# 12_-_CONNECTOR.net
KiCad netlist of a schematic drawn in Altium Designer
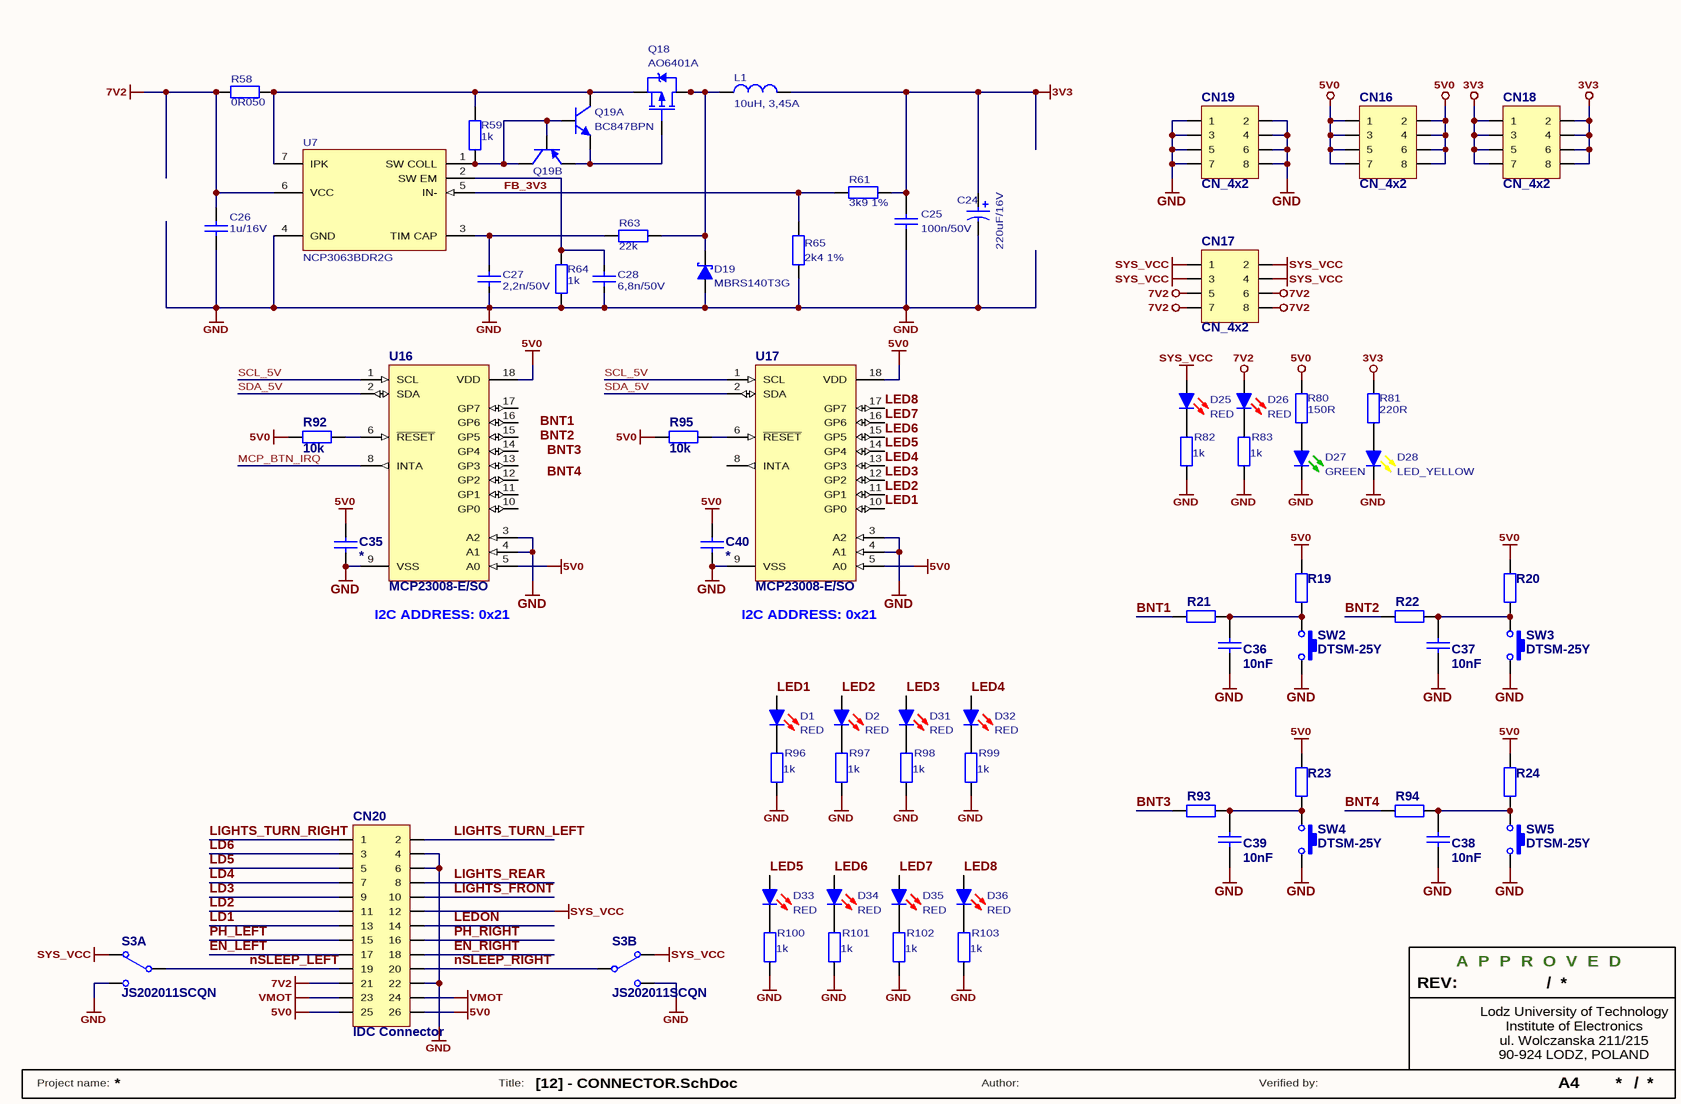
[diagram p0: [12] - CONNECTOR.SchDoc]

(export (version "E")
  (design (tool "Eeschema 10.0.6"))
  (components
    (comp (ref "C24")
      (value "220uF/16V")
      (footprint "CES_E_8.3x8.3_6.2")
      (description "Polarized Capacitor")
      (libsource (lib "capacitors") (part "Cap Pol"))
    )
    (comp (ref "C25")
      (value "100n/50V")
      (footprint "C0805")
      (description "Capacitor")
      (libsource (lib "capacitors") (part "Cap"))
    )
    (comp (ref "C26")
      (value "1u/16V")
      (footprint "C0805")
      (description "Capacitor")
      (libsource (lib "") (part "Cap_2"))
    )
    (comp (ref "C27")
      (value "2,2n/50V")
      (footprint "C0805")
      (description "Capacitor")
      (libsource (lib "") (part "Cap_1"))
    )
    (comp (ref "C28")
      (value "6,8n/50V")
      (footprint "C0805")
      (description "Capacitor")
      (libsource (lib "") (part "Cap_1"))
    )
    (comp (ref "C35")
      (value "*")
      (footprint "C0805")
      (description "Capacitor")
      (fields (field (name "ALTIUM_VALUE") "*"))
      (libsource (lib "") (part "Cap_2"))
    )
    (comp (ref "C36")
      (value "10nF")
      (footprint "C0805")
      (description "Capacitor")
      (libsource (lib "capacitors") (part "Cap"))
    )
    (comp (ref "C37")
      (value "10nF")
      (footprint "C0805")
      (description "Capacitor")
      (libsource (lib "capacitors") (part "Cap"))
    )
    (comp (ref "C38")
      (value "10nF")
      (footprint "C0805")
      (description "Capacitor")
      (libsource (lib "capacitors") (part "Cap"))
    )
    (comp (ref "C39")
      (value "10nF")
      (footprint "C0805")
      (description "Capacitor")
      (libsource (lib "capacitors") (part "Cap"))
    )
    (comp (ref "C40")
      (value "*")
      (footprint "C0805")
      (description "Capacitor")
      (fields (field (name "ALTIUM_VALUE") "*"))
      (libsource (lib "") (part "Cap_2"))
    )
    (comp (ref "CN16") (value "CN_4x2") (footprint "GP_4x2") (libsource (lib "goldpin_male") (part "CN_4x2")))
    (comp (ref "CN17") (value "CN_4x2") (footprint "GP_4x2") (libsource (lib "goldpin_male") (part "CN_4x2")))
    (comp (ref "CN18") (value "CN_4x2") (footprint "GP_4x2") (libsource (lib "goldpin_male") (part "CN_4x2")))
    (comp (ref "CN19") (value "CN_4x2") (footprint "GP_4x2") (libsource (lib "goldpin_male") (part "CN_4x2")))
    (comp (ref "CN20")
      (value "IDC Connector")
      (footprint "IDC26_RA")
      (libsource (lib "idc") (part "CN_13x2"))
    )
    (comp (ref "D1")
      (value "RED")
      (footprint "LED0805R")
      (description "RED LED")
      (libsource (lib "leds") (part "LED_RED"))
    )
    (comp (ref "D2")
      (value "RED")
      (footprint "LED0805R")
      (description "RED LED")
      (libsource (lib "leds") (part "LED_RED"))
    )
    (comp (ref "D19")
      (value "MBRS140T3G")
      (footprint "SMB")
      (description "Schottky barrier rectifier: 40V, 1A")
      (libsource (lib "diodes_schottky") (part "MBRS140T3G"))
    )
    (comp (ref "D25")
      (value "RED")
      (footprint "LED0805R")
      (description "RED LED")
      (libsource (lib "leds") (part "LED_RED"))
    )
    (comp (ref "D26")
      (value "RED")
      (footprint "LED0805R")
      (description "RED LED")
      (libsource (lib "leds") (part "LED_RED"))
    )
    (comp (ref "D27")
      (value "GREEN")
      (footprint "LED0805G")
      (description "GREEN LED")
      (libsource (lib "leds") (part "LED_GREEN"))
    )
    (comp (ref "D28")
      (value "LED_YELLOW")
      (footprint "LED0805Y")
      (description "YELLOW LED")
      (libsource (lib "leds") (part "LED_YELLOW"))
    )
    (comp (ref "D31")
      (value "RED")
      (footprint "LED0805R")
      (description "RED LED")
      (libsource (lib "leds") (part "LED_RED"))
    )
    (comp (ref "D32")
      (value "RED")
      (footprint "LED0805R")
      (description "RED LED")
      (libsource (lib "leds") (part "LED_RED"))
    )
    (comp (ref "D33")
      (value "RED")
      (footprint "LED0805R")
      (description "RED LED")
      (libsource (lib "leds") (part "LED_RED"))
    )
    (comp (ref "D34")
      (value "RED")
      (footprint "LED0805R")
      (description "RED LED")
      (libsource (lib "leds") (part "LED_RED"))
    )
    (comp (ref "D35")
      (value "RED")
      (footprint "LED0805R")
      (description "RED LED")
      (libsource (lib "leds") (part "LED_RED"))
    )
    (comp (ref "D36")
      (value "RED")
      (footprint "LED0805R")
      (description "RED LED")
      (libsource (lib "leds") (part "LED_RED"))
    )
    (comp (ref "L1")
      (value "10uH, 3,45A")
      (footprint "PSDB1005")
      (description "10uH, 20%, 3,45A, PSDB1005N Series Inductor")
      (libsource (lib "inductors") (part "PSDB1005NT100"))
    )
    (comp (ref "Q18")
      (value "AO6401A")
      (footprint "SOT-23-6")
      (description "P-Channel MOSFET; -60V, -5A, 1.3W;")
      (libsource (lib "transistors_mos") (part "AO6401A"))
    )
    (comp (ref "Q19")
      (value "BC847BPN")
      (footprint "SOT-323-6 (SOT-363, SC88, SC70-6)")
      (description "PNP/NPN General Purpose Transistor (VCE=45V, IC=100mA)")
      (libsource (lib "transistors_bjt") (part "BC847BPN"))
    )
    (comp (ref "R19")
      (value "~")
      (footprint "R0805")
      (description "Resistor")
      (libsource (lib "") (part "Res_1"))
    )
    (comp (ref "R20")
      (value "~")
      (footprint "R0805")
      (description "Resistor")
      (libsource (lib "") (part "Res_1"))
    )
    (comp (ref "R21")
      (value "~")
      (footprint "R0805")
      (description "Resistor")
      (libsource (lib "") (part "Res_4"))
    )
    (comp (ref "R22")
      (value "~")
      (footprint "R0805")
      (description "Resistor")
      (libsource (lib "") (part "Res_4"))
    )
    (comp (ref "R23")
      (value "~")
      (footprint "R0805")
      (description "Resistor")
      (libsource (lib "") (part "Res_1"))
    )
    (comp (ref "R24")
      (value "~")
      (footprint "R0805")
      (description "Resistor")
      (libsource (lib "") (part "Res_1"))
    )
    (comp (ref "R58")
      (value "0R050")
      (footprint "R0805")
      (description "Resistor")
      (libsource (lib "") (part "Res_3"))
    )
    (comp (ref "R59")
      (value "1k")
      (footprint "R0805")
      (description "Resistor")
      (libsource (lib "resistors") (part "Res"))
    )
    (comp (ref "R61")
      (value "3k9 1%")
      (footprint "R0805")
      (description "Resistor")
      (libsource (lib "") (part "Res_3"))
    )
    (comp (ref "R63")
      (value "22k")
      (footprint "R0805")
      (description "Resistor")
      (libsource (lib "") (part "Res_2"))
    )
    (comp (ref "R64")
      (value "1k")
      (footprint "R0805")
      (description "Resistor")
      (libsource (lib "resistors") (part "Res"))
    )
    (comp (ref "R65")
      (value "2k4 1%")
      (footprint "R0805")
      (description "Resistor")
      (libsource (lib "resistors") (part "Res"))
    )
    (comp (ref "R80")
      (value "150R")
      (footprint "R0805")
      (description "Resistor")
      (libsource (lib "resistors") (part "Res"))
    )
    (comp (ref "R81")
      (value "220R")
      (footprint "R0805")
      (description "Resistor")
      (libsource (lib "resistors") (part "Res"))
    )
    (comp (ref "R82")
      (value "1k")
      (footprint "R0805")
      (description "Resistor")
      (libsource (lib "resistors") (part "Res"))
    )
    (comp (ref "R83")
      (value "1k")
      (footprint "R0805")
      (description "Resistor")
      (libsource (lib "resistors") (part "Res"))
    )
    (comp (ref "R92")
      (value "10k")
      (footprint "R0805")
      (description "Resistor")
      (libsource (lib "") (part "Res_3"))
    )
    (comp (ref "R93")
      (value "~")
      (footprint "R0805")
      (description "Resistor")
      (libsource (lib "") (part "Res_4"))
    )
    (comp (ref "R94")
      (value "~")
      (footprint "R0805")
      (description "Resistor")
      (libsource (lib "") (part "Res_4"))
    )
    (comp (ref "R95")
      (value "10k")
      (footprint "R0805")
      (description "Resistor")
      (libsource (lib "") (part "Res_3"))
    )
    (comp (ref "R96")
      (value "1k")
      (footprint "R0805")
      (description "Resistor")
      (libsource (lib "resistors") (part "Res"))
    )
    (comp (ref "R97")
      (value "1k")
      (footprint "R0805")
      (description "Resistor")
      (libsource (lib "resistors") (part "Res"))
    )
    (comp (ref "R98")
      (value "1k")
      (footprint "R0805")
      (description "Resistor")
      (libsource (lib "resistors") (part "Res"))
    )
    (comp (ref "R99")
      (value "1k")
      (footprint "R0805")
      (description "Resistor")
      (libsource (lib "resistors") (part "Res"))
    )
    (comp (ref "R100")
      (value "1k")
      (footprint "R0805")
      (description "Resistor")
      (libsource (lib "resistors") (part "Res"))
    )
    (comp (ref "R101")
      (value "1k")
      (footprint "R0805")
      (description "Resistor")
      (libsource (lib "resistors") (part "Res"))
    )
    (comp (ref "R102")
      (value "1k")
      (footprint "R0805")
      (description "Resistor")
      (libsource (lib "resistors") (part "Res"))
    )
    (comp (ref "R103")
      (value "1k")
      (footprint "R0805")
      (description "Resistor")
      (libsource (lib "resistors") (part "Res"))
    )
    (comp (ref "S3")
      (value "JS202011SCQN")
      (footprint "JS202011SCQN")
      (description "C&K JS202011SCQN DPDT Switch")
      (fields (field (name "PUBLISHER") "Altium Limited"))
      (libsource (lib "switches_slide") (part "JS202011SCQN"))
    )
    (comp (ref "SW2")
      (value "DTSM-25Y")
      (footprint "DTSM-25Y")
      (description "DIPTRONICS Yellow 12x12mm SMD Tactile SPST-NO Switch")
      (libsource (lib "microswitches") (part "DTSM-25Y"))
    )
    (comp (ref "SW3")
      (value "DTSM-25Y")
      (footprint "DTSM-25Y")
      (description "DIPTRONICS Yellow 12x12mm SMD Tactile SPST-NO Switch")
      (libsource (lib "microswitches") (part "DTSM-25Y"))
    )
    (comp (ref "SW4")
      (value "DTSM-25Y")
      (footprint "DTSM-25Y")
      (description "DIPTRONICS Yellow 12x12mm SMD Tactile SPST-NO Switch")
      (libsource (lib "microswitches") (part "DTSM-25Y"))
    )
    (comp (ref "SW5")
      (value "DTSM-25Y")
      (footprint "DTSM-25Y")
      (description "DIPTRONICS Yellow 12x12mm SMD Tactile SPST-NO Switch")
      (libsource (lib "microswitches") (part "DTSM-25Y"))
    )
    (comp (ref "U7")
      (value "NCP3063BDR2G")
      (footprint "SO8")
      (description "DC-DC Converter NCP3063BDR2G (Farnell 1547126)")
      (libsource (lib "switched_voltage_regulators") (part "NCP3063BDR2G"))
    )
    (comp (ref "U16")
      (value "MCP23008-E/SO")
      (footprint "SO18W")
      (description "8-Bit I/O Expander with Serial Interface I2C, 18-Pin SOIC Package")
      (libsource (lib "io_expanders") (part "MCP23008-E/SO"))
    )
    (comp (ref "U17")
      (value "MCP23008-E/SO")
      (footprint "SO18W")
      (description "8-Bit I/O Expander with Serial Interface I2C, 18-Pin SOIC Package")
      (libsource (lib "io_expanders") (part "MCP23008-E/SO"))
    )
  )
  (nets
    (net (code "1") (name "/BNT1") (class "Default")
      (node (ref "R21") (pin "1") (pinfunction "1_1") (pintype "passive"))
    )
    (net (code "2") (name "/BNT2") (class "Default")
      (node (ref "R22") (pin "1") (pinfunction "1_1") (pintype "passive"))
    )
    (net (code "3") (name "/BNT3") (class "Default")
      (node (ref "R93") (pin "1") (pinfunction "1_1") (pintype "passive"))
    )
    (net (code "4") (name "/BNT4") (class "Default")
      (node (ref "R94") (pin "1") (pinfunction "1_1") (pintype "passive"))
    )
    (net (code "5") (name "/EN_LEFT") (class "Default")
      (node (ref "CN20") (pin "17") (pinfunction "17_17") (pintype "passive"))
    )
    (net (code "6") (name "/EN_RIGHT") (class "Default")
      (node (ref "CN20") (pin "18") (pinfunction "18_18") (pintype "passive"))
    )
    (net (code "7") (name "/FB_3V3") (class "Default")
      (node (ref "R61") (pin "1") (pinfunction "1_1") (pintype "passive"))
      (node (ref "R65") (pin "1") (pinfunction "1_1") (pintype "passive"))
      (node (ref "U7") (pin "5") (pinfunction "IN-_5") (pintype "input"))
    )
    (net (code "8") (name "/LD1") (class "Default")
      (node (ref "CN20") (pin "13") (pinfunction "13_13") (pintype "passive"))
    )
    (net (code "9") (name "/LD2") (class "Default")
      (node (ref "CN20") (pin "11") (pinfunction "11_11") (pintype "passive"))
    )
    (net (code "10") (name "/LD3") (class "Default")
      (node (ref "CN20") (pin "9") (pinfunction "9_9") (pintype "passive"))
    )
    (net (code "11") (name "/LD4") (class "Default")
      (node (ref "CN20") (pin "7") (pinfunction "7_7") (pintype "passive"))
    )
    (net (code "12") (name "/LD5") (class "Default")
      (node (ref "CN20") (pin "5") (pinfunction "5_5") (pintype "passive"))
    )
    (net (code "13") (name "/LD6") (class "Default")
      (node (ref "CN20") (pin "3") (pinfunction "3_3") (pintype "passive"))
    )
    (net (code "14") (name "/LED1") (class "Default")
      (node (ref "D1") (pin "1") (pinfunction "A_1") (pintype "passive"))
      (node (ref "U17") (pin "10") (pinfunction "GP0_10") (pintype "bidirectional"))
    )
    (net (code "15") (name "/LED2") (class "Default")
      (node (ref "D2") (pin "1") (pinfunction "A_1") (pintype "passive"))
      (node (ref "U17") (pin "11") (pinfunction "GP1_11") (pintype "bidirectional"))
    )
    (net (code "16") (name "/LED3") (class "Default")
      (node (ref "D31") (pin "1") (pinfunction "A_1") (pintype "passive"))
      (node (ref "U17") (pin "12") (pinfunction "GP2_12") (pintype "bidirectional"))
    )
    (net (code "17") (name "/LED4") (class "Default")
      (node (ref "D32") (pin "1") (pinfunction "A_1") (pintype "passive"))
      (node (ref "U17") (pin "13") (pinfunction "GP3_13") (pintype "bidirectional"))
    )
    (net (code "18") (name "/LED5") (class "Default")
      (node (ref "D33") (pin "1") (pinfunction "A_1") (pintype "passive"))
      (node (ref "U17") (pin "14") (pinfunction "GP4_14") (pintype "bidirectional"))
    )
    (net (code "19") (name "/LED6") (class "Default")
      (node (ref "D34") (pin "1") (pinfunction "A_1") (pintype "passive"))
      (node (ref "U17") (pin "15") (pinfunction "GP5_15") (pintype "bidirectional"))
    )
    (net (code "20") (name "/LED7") (class "Default")
      (node (ref "D35") (pin "1") (pinfunction "A_1") (pintype "passive"))
      (node (ref "U17") (pin "16") (pinfunction "GP6_16") (pintype "bidirectional"))
    )
    (net (code "21") (name "/LED8") (class "Default")
      (node (ref "D36") (pin "1") (pinfunction "A_1") (pintype "passive"))
      (node (ref "U17") (pin "17") (pinfunction "GP7_17") (pintype "bidirectional"))
    )
    (net (code "22") (name "/LEDON") (class "Default")
      (node (ref "CN20") (pin "14") (pinfunction "14_14") (pintype "passive"))
    )
    (net (code "23") (name "/LIGHTS_FRONT") (class "Default")
      (node (ref "CN20") (pin "10") (pinfunction "10_10") (pintype "passive"))
    )
    (net (code "24") (name "/LIGHTS_REAR") (class "Default")
      (node (ref "CN20") (pin "8") (pinfunction "8_8") (pintype "passive"))
    )
    (net (code "25") (name "/LIGHTS_TURN_LEFT") (class "Default")
      (node (ref "CN20") (pin "2") (pinfunction "2_2") (pintype "passive"))
    )
    (net (code "26") (name "/LIGHTS_TURN_RIGHT") (class "Default")
      (node (ref "CN20") (pin "1") (pinfunction "1_1") (pintype "passive"))
    )
    (net (code "27") (name "/MCP_BTN_IRQ") (class "Default")
      (node (ref "U16") (pin "8") (pinfunction "INTA_8") (pintype "output"))
    )
    (net (code "28") (name "/PH_LEFT") (class "Default")
      (node (ref "CN20") (pin "15") (pinfunction "15_15") (pintype "passive"))
    )
    (net (code "29") (name "/PH_RIGHT") (class "Default")
      (node (ref "CN20") (pin "16") (pinfunction "16_16") (pintype "passive"))
    )
    (net (code "30") (name "/SCL_5V") (class "Default")
      (node (ref "U16") (pin "1") (pinfunction "SCL_1") (pintype "input"))
      (node (ref "U17") (pin "1") (pinfunction "SCL_1") (pintype "input"))
    )
    (net (code "31") (name "/SDA_5V") (class "Default")
      (node (ref "U16") (pin "2") (pinfunction "SDA_2") (pintype "bidirectional"))
      (node (ref "U17") (pin "2") (pinfunction "SDA_2") (pintype "bidirectional"))
    )
    (net (code "32") (name "/nSLEEP_LEFT") (class "Default")
      (node (ref "CN20") (pin "19") (pinfunction "19_19") (pintype "passive"))
      (node (ref "S3") (pin "1") (pinfunction "COMMON1_1") (pintype "passive"))
    )
    (net (code "33") (name "/nSLEEP_RIGHT") (class "Default")
      (node (ref "CN20") (pin "20") (pinfunction "20_20") (pintype "passive"))
      (node (ref "S3") (pin "5") (pinfunction "COMMON2_5") (pintype "passive"))
    )
    (net (code "34") (name "3V3") (class "Default")
      (node (ref "C24") (pin "1") (pinfunction "1_1") (pintype "passive"))
      (node (ref "C25") (pin "2") (pinfunction "2_2") (pintype "passive"))
      (node (ref "CN18") (pin "1") (pinfunction "1_1") (pintype "passive"))
      (node (ref "CN18") (pin "2") (pinfunction "2_2") (pintype "passive"))
      (node (ref "CN18") (pin "3") (pinfunction "3_3") (pintype "passive"))
      (node (ref "CN18") (pin "4") (pinfunction "4_4") (pintype "passive"))
      (node (ref "CN18") (pin "5") (pinfunction "5_5") (pintype "passive"))
      (node (ref "CN18") (pin "6") (pinfunction "6_6") (pintype "passive"))
      (node (ref "CN18") (pin "7") (pinfunction "7_7") (pintype "passive"))
      (node (ref "CN18") (pin "8") (pinfunction "8_8") (pintype "passive"))
      (node (ref "L1") (pin "2") (pinfunction "2_2") (pintype "passive"))
      (node (ref "R61") (pin "2") (pinfunction "2_2") (pintype "passive"))
      (node (ref "R81") (pin "1") (pinfunction "1_1") (pintype "passive"))
    )
    (net (code "35") (name "5V0") (class "Default")
      (node (ref "C35") (pin "2") (pinfunction "2_2") (pintype "passive"))
      (node (ref "C40") (pin "2") (pinfunction "2_2") (pintype "passive"))
      (node (ref "CN16") (pin "1") (pinfunction "1_1") (pintype "passive"))
      (node (ref "CN16") (pin "2") (pinfunction "2_2") (pintype "passive"))
      (node (ref "CN16") (pin "3") (pinfunction "3_3") (pintype "passive"))
      (node (ref "CN16") (pin "4") (pinfunction "4_4") (pintype "passive"))
      (node (ref "CN16") (pin "5") (pinfunction "5_5") (pintype "passive"))
      (node (ref "CN16") (pin "6") (pinfunction "6_6") (pintype "passive"))
      (node (ref "CN16") (pin "7") (pinfunction "7_7") (pintype "passive"))
      (node (ref "CN16") (pin "8") (pinfunction "8_8") (pintype "passive"))
      (node (ref "CN20") (pin "25") (pinfunction "25_25") (pintype "passive"))
      (node (ref "CN20") (pin "26") (pinfunction "26_26") (pintype "passive"))
      (node (ref "R19") (pin "2") (pinfunction "2_2") (pintype "passive"))
      (node (ref "R20") (pin "2") (pinfunction "2_2") (pintype "passive"))
      (node (ref "R23") (pin "2") (pinfunction "2_2") (pintype "passive"))
      (node (ref "R24") (pin "2") (pinfunction "2_2") (pintype "passive"))
      (node (ref "R80") (pin "1") (pinfunction "1_1") (pintype "passive"))
      (node (ref "R92") (pin "1") (pinfunction "1_1") (pintype "passive"))
      (node (ref "R95") (pin "1") (pinfunction "1_1") (pintype "passive"))
      (node (ref "U16") (pin "18") (pinfunction "VDD_18") (pintype "power_in"))
      (node (ref "U16") (pin "5") (pinfunction "A0_5") (pintype "input"))
      (node (ref "U17") (pin "18") (pinfunction "VDD_18") (pintype "power_in"))
      (node (ref "U17") (pin "5") (pinfunction "A0_5") (pintype "input"))
    )
    (net (code "36") (name "7V2") (class "Default")
      (node (ref "C26") (pin "2") (pinfunction "2_2") (pintype "passive"))
      (node (ref "CN17") (pin "5") (pinfunction "5_5") (pintype "passive"))
      (node (ref "CN17") (pin "6") (pinfunction "6_6") (pintype "passive"))
      (node (ref "CN17") (pin "7") (pinfunction "7_7") (pintype "passive"))
      (node (ref "CN17") (pin "8") (pinfunction "8_8") (pintype "passive"))
      (node (ref "CN20") (pin "21") (pinfunction "21_21") (pintype "passive"))
      (node (ref "D26") (pin "1") (pinfunction "A_1") (pintype "passive"))
      (node (ref "R58") (pin "1") (pinfunction "1_1") (pintype "passive"))
      (node (ref "U7") (pin "6") (pinfunction "VCC_6") (pintype "power_in"))
    )
    (net (code "37") (name "GND") (class "Default")
      (node (ref "C24") (pin "2") (pinfunction "2_2") (pintype "passive"))
      (node (ref "C25") (pin "1") (pinfunction "1_1") (pintype "passive"))
      (node (ref "C26") (pin "1") (pinfunction "1_1") (pintype "passive"))
      (node (ref "C27") (pin "1") (pinfunction "1_1") (pintype "passive"))
      (node (ref "C28") (pin "1") (pinfunction "1_1") (pintype "passive"))
      (node (ref "C35") (pin "1") (pinfunction "1_1") (pintype "passive"))
      (node (ref "C36") (pin "1") (pinfunction "1_1") (pintype "passive"))
      (node (ref "C37") (pin "1") (pinfunction "1_1") (pintype "passive"))
      (node (ref "C38") (pin "1") (pinfunction "1_1") (pintype "passive"))
      (node (ref "C39") (pin "1") (pinfunction "1_1") (pintype "passive"))
      (node (ref "C40") (pin "1") (pinfunction "1_1") (pintype "passive"))
      (node (ref "CN19") (pin "1") (pinfunction "1_1") (pintype "passive"))
      (node (ref "CN19") (pin "2") (pinfunction "2_2") (pintype "passive"))
      (node (ref "CN19") (pin "3") (pinfunction "3_3") (pintype "passive"))
      (node (ref "CN19") (pin "4") (pinfunction "4_4") (pintype "passive"))
      (node (ref "CN19") (pin "5") (pinfunction "5_5") (pintype "passive"))
      (node (ref "CN19") (pin "6") (pinfunction "6_6") (pintype "passive"))
      (node (ref "CN19") (pin "7") (pinfunction "7_7") (pintype "passive"))
      (node (ref "CN19") (pin "8") (pinfunction "8_8") (pintype "passive"))
      (node (ref "CN20") (pin "22") (pinfunction "22_22") (pintype "passive"))
      (node (ref "CN20") (pin "4") (pinfunction "4_4") (pintype "passive"))
      (node (ref "CN20") (pin "6") (pinfunction "6_6") (pintype "passive"))
      (node (ref "D19") (pin "1") (pinfunction "A_1") (pintype "passive"))
      (node (ref "D27") (pin "2") (pinfunction "K_2") (pintype "passive"))
      (node (ref "D28") (pin "2") (pinfunction "K_2") (pintype "passive"))
      (node (ref "R100") (pin "2") (pinfunction "2_2") (pintype "passive"))
      (node (ref "R101") (pin "2") (pinfunction "2_2") (pintype "passive"))
      (node (ref "R102") (pin "2") (pinfunction "2_2") (pintype "passive"))
      (node (ref "R103") (pin "2") (pinfunction "2_2") (pintype "passive"))
      (node (ref "R64") (pin "2") (pinfunction "2_2") (pintype "passive"))
      (node (ref "R65") (pin "2") (pinfunction "2_2") (pintype "passive"))
      (node (ref "R82") (pin "2") (pinfunction "2_2") (pintype "passive"))
      (node (ref "R83") (pin "2") (pinfunction "2_2") (pintype "passive"))
      (node (ref "R96") (pin "2") (pinfunction "2_2") (pintype "passive"))
      (node (ref "R97") (pin "2") (pinfunction "2_2") (pintype "passive"))
      (node (ref "R98") (pin "2") (pinfunction "2_2") (pintype "passive"))
      (node (ref "R99") (pin "2") (pinfunction "2_2") (pintype "passive"))
      (node (ref "S3") (pin "3") (pinfunction "NO1_3") (pintype "passive"))
      (node (ref "S3") (pin "6") (pinfunction "NO2_6") (pintype "passive"))
      (node (ref "SW2") (pin "2") (pinfunction "2_2") (pintype "passive"))
      (node (ref "SW3") (pin "2") (pinfunction "2_2") (pintype "passive"))
      (node (ref "SW4") (pin "2") (pinfunction "2_2") (pintype "passive"))
      (node (ref "SW5") (pin "2") (pinfunction "2_2") (pintype "passive"))
      (node (ref "U16") (pin "3") (pinfunction "A2_3") (pintype "input"))
      (node (ref "U16") (pin "4") (pinfunction "A1_4") (pintype "input"))
      (node (ref "U16") (pin "9") (pinfunction "VSS_9") (pintype "power_in"))
      (node (ref "U17") (pin "3") (pinfunction "A2_3") (pintype "input"))
      (node (ref "U17") (pin "4") (pinfunction "A1_4") (pintype "input"))
      (node (ref "U17") (pin "9") (pinfunction "VSS_9") (pintype "power_in"))
      (node (ref "U7") (pin "4") (pinfunction "GND_4") (pintype "power_in"))
    )
    (net (code "38") (name "Net-(C36-Pad2)") (class "Default")
      (node (ref "C36") (pin "2") (pinfunction "2_2") (pintype "passive"))
      (node (ref "R19") (pin "1") (pinfunction "1_1") (pintype "passive"))
      (node (ref "R21") (pin "2") (pinfunction "2_2") (pintype "passive"))
      (node (ref "SW2") (pin "1") (pinfunction "1_1") (pintype "passive"))
    )
    (net (code "39") (name "Net-(C37-Pad2)") (class "Default")
      (node (ref "C37") (pin "2") (pinfunction "2_2") (pintype "passive"))
      (node (ref "R20") (pin "1") (pinfunction "1_1") (pintype "passive"))
      (node (ref "R22") (pin "2") (pinfunction "2_2") (pintype "passive"))
      (node (ref "SW3") (pin "1") (pinfunction "1_1") (pintype "passive"))
    )
    (net (code "40") (name "Net-(C38-Pad2)") (class "Default")
      (node (ref "C38") (pin "2") (pinfunction "2_2") (pintype "passive"))
      (node (ref "R24") (pin "1") (pinfunction "1_1") (pintype "passive"))
      (node (ref "R94") (pin "2") (pinfunction "2_2") (pintype "passive"))
      (node (ref "SW5") (pin "1") (pinfunction "1_1") (pintype "passive"))
    )
    (net (code "41") (name "Net-(C39-Pad2)") (class "Default")
      (node (ref "C39") (pin "2") (pinfunction "2_2") (pintype "passive"))
      (node (ref "R23") (pin "1") (pinfunction "1_1") (pintype "passive"))
      (node (ref "R93") (pin "2") (pinfunction "2_2") (pintype "passive"))
      (node (ref "SW4") (pin "1") (pinfunction "1_1") (pintype "passive"))
    )
    (net (code "42") (name "Net-(D1-K)") (class "Default")
      (node (ref "D1") (pin "2") (pinfunction "K_2") (pintype "passive"))
      (node (ref "R96") (pin "1") (pinfunction "1_1") (pintype "passive"))
    )
    (net (code "43") (name "Net-(D2-K)") (class "Default")
      (node (ref "D2") (pin "2") (pinfunction "K_2") (pintype "passive"))
      (node (ref "R97") (pin "1") (pinfunction "1_1") (pintype "passive"))
    )
    (net (code "44") (name "Net-(D19-K)") (class "Default")
      (node (ref "D19") (pin "2") (pinfunction "K_2") (pintype "passive"))
      (node (ref "L1") (pin "1") (pinfunction "1_1") (pintype "passive"))
      (node (ref "Q18") (pin "1") (pinfunction "D_1") (pintype "passive"))
      (node (ref "Q18") (pin "2") (pinfunction "D_2") (pintype "passive"))
      (node (ref "Q18") (pin "5") (pinfunction "D_5") (pintype "passive"))
      (node (ref "Q18") (pin "6") (pinfunction "D_6") (pintype "passive"))
      (node (ref "R63") (pin "1") (pinfunction "1_1") (pintype "passive"))
    )
    (net (code "45") (name "Net-(D25-K)") (class "Default")
      (node (ref "D25") (pin "2") (pinfunction "K_2") (pintype "passive"))
      (node (ref "R82") (pin "1") (pinfunction "1_1") (pintype "passive"))
    )
    (net (code "46") (name "Net-(D26-K)") (class "Default")
      (node (ref "D26") (pin "2") (pinfunction "K_2") (pintype "passive"))
      (node (ref "R83") (pin "1") (pinfunction "1_1") (pintype "passive"))
    )
    (net (code "47") (name "Net-(D27-A)") (class "Default")
      (node (ref "D27") (pin "1") (pinfunction "A_1") (pintype "passive"))
      (node (ref "R80") (pin "2") (pinfunction "2_2") (pintype "passive"))
    )
    (net (code "48") (name "Net-(D28-A)") (class "Default")
      (node (ref "D28") (pin "1") (pinfunction "A_1") (pintype "passive"))
      (node (ref "R81") (pin "2") (pinfunction "2_2") (pintype "passive"))
    )
    (net (code "49") (name "Net-(D31-K)") (class "Default")
      (node (ref "D31") (pin "2") (pinfunction "K_2") (pintype "passive"))
      (node (ref "R98") (pin "1") (pinfunction "1_1") (pintype "passive"))
    )
    (net (code "50") (name "Net-(D32-K)") (class "Default")
      (node (ref "D32") (pin "2") (pinfunction "K_2") (pintype "passive"))
      (node (ref "R99") (pin "1") (pinfunction "1_1") (pintype "passive"))
    )
    (net (code "51") (name "Net-(D33-K)") (class "Default")
      (node (ref "D33") (pin "2") (pinfunction "K_2") (pintype "passive"))
      (node (ref "R100") (pin "1") (pinfunction "1_1") (pintype "passive"))
    )
    (net (code "52") (name "Net-(D34-K)") (class "Default")
      (node (ref "D34") (pin "2") (pinfunction "K_2") (pintype "passive"))
      (node (ref "R101") (pin "1") (pinfunction "1_1") (pintype "passive"))
    )
    (net (code "53") (name "Net-(D35-K)") (class "Default")
      (node (ref "D35") (pin "2") (pinfunction "K_2") (pintype "passive"))
      (node (ref "R102") (pin "1") (pinfunction "1_1") (pintype "passive"))
    )
    (net (code "54") (name "Net-(D36-K)") (class "Default")
      (node (ref "D36") (pin "2") (pinfunction "K_2") (pintype "passive"))
      (node (ref "R103") (pin "1") (pinfunction "1_1") (pintype "passive"))
    )
    (net (code "55") (name "Net-(Q18-G)") (class "Default")
      (node (ref "Q18") (pin "3") (pinfunction "G_3") (pintype "passive"))
      (node (ref "Q19") (pin "1") (pinfunction "EA_1") (pintype "passive"))
      (node (ref "Q19") (pin "4") (pinfunction "EB_4") (pintype "passive"))
    )
    (net (code "56") (name "Net-(Q18-S)") (class "Default")
      (node (ref "Q18") (pin "4") (pinfunction "S_4") (pintype "passive"))
      (node (ref "Q19") (pin "6") (pinfunction "CA_6") (pintype "passive"))
      (node (ref "R58") (pin "2") (pinfunction "2_2") (pintype "passive"))
      (node (ref "R59") (pin "1") (pinfunction "1_1") (pintype "passive"))
      (node (ref "U7") (pin "7") (pinfunction "IPK_7") (pintype "passive"))
    )
    (net (code "57") (name "Net-(Q19A-BA)") (class "Default")
      (node (ref "Q19") (pin "2") (pinfunction "BA_2") (pintype "passive"))
      (node (ref "Q19") (pin "3") (pinfunction "CB_3") (pintype "passive"))
      (node (ref "Q19") (pin "5") (pinfunction "BB_5") (pintype "passive"))
      (node (ref "R59") (pin "2") (pinfunction "2_2") (pintype "passive"))
      (node (ref "U7") (pin "1") (pinfunction "SW_COLL_1") (pintype "passive"))
    )
    (net (code "58") (name "Net-(U7-SW_EM)") (class "Default")
      (node (ref "C28") (pin "2") (pinfunction "2_2") (pintype "passive"))
      (node (ref "R64") (pin "1") (pinfunction "1_1") (pintype "passive"))
      (node (ref "U7") (pin "2") (pinfunction "SW_EM_2") (pintype "passive"))
    )
    (net (code "59") (name "Net-(U7-TIM_CAP)") (class "Default")
      (node (ref "C27") (pin "2") (pinfunction "2_2") (pintype "passive"))
      (node (ref "R63") (pin "2") (pinfunction "2_2") (pintype "passive"))
      (node (ref "U7") (pin "3") (pinfunction "TIM_CAP_3") (pintype "passive"))
    )
    (net (code "60") (name "Net-(U16-~{RESET})") (class "Default")
      (node (ref "R92") (pin "2") (pinfunction "2_2") (pintype "passive"))
      (node (ref "U16") (pin "6") (pinfunction "~{RESET}_6") (pintype "input"))
    )
    (net (code "61") (name "Net-(U17-~{RESET})") (class "Default")
      (node (ref "R95") (pin "2") (pinfunction "2_2") (pintype "passive"))
      (node (ref "U17") (pin "6") (pinfunction "~{RESET}_6") (pintype "input"))
    )
    (net (code "62") (name "SYS_VCC") (class "Default")
      (node (ref "CN17") (pin "1") (pinfunction "1_1") (pintype "passive"))
      (node (ref "CN17") (pin "2") (pinfunction "2_2") (pintype "passive"))
      (node (ref "CN17") (pin "3") (pinfunction "3_3") (pintype "passive"))
      (node (ref "CN17") (pin "4") (pinfunction "4_4") (pintype "passive"))
      (node (ref "CN20") (pin "12") (pinfunction "12_12") (pintype "passive"))
      (node (ref "D25") (pin "1") (pinfunction "A_1") (pintype "passive"))
      (node (ref "S3") (pin "2") (pinfunction "NC1_2") (pintype "passive"))
      (node (ref "S3") (pin "4") (pinfunction "NC2_4") (pintype "passive"))
    )
    (net (code "63") (name "VMOT") (class "Default")
      (node (ref "CN20") (pin "23") (pinfunction "23_23") (pintype "passive"))
      (node (ref "CN20") (pin "24") (pinfunction "24_24") (pintype "passive"))
    )
    (net (code "64") (name "unconnected-(U16-GP0-Pad10)") (class "Default")
      (node (ref "U16") (pin "10") (pinfunction "GP0_10") (pintype "bidirectional"))
    )
    (net (code "65") (name "unconnected-(U16-GP1-Pad11)") (class "Default")
      (node (ref "U16") (pin "11") (pinfunction "GP1_11") (pintype "bidirectional"))
    )
    (net (code "66") (name "unconnected-(U16-GP2-Pad12)") (class "Default")
      (node (ref "U16") (pin "12") (pinfunction "GP2_12") (pintype "bidirectional"))
    )
    (net (code "67") (name "unconnected-(U16-GP3-Pad13)") (class "Default")
      (node (ref "U16") (pin "13") (pinfunction "GP3_13") (pintype "bidirectional"))
    )
    (net (code "68") (name "unconnected-(U16-GP4-Pad14)") (class "Default")
      (node (ref "U16") (pin "14") (pinfunction "GP4_14") (pintype "bidirectional"))
    )
    (net (code "69") (name "unconnected-(U16-GP5-Pad15)") (class "Default")
      (node (ref "U16") (pin "15") (pinfunction "GP5_15") (pintype "bidirectional"))
    )
    (net (code "70") (name "unconnected-(U16-GP6-Pad16)") (class "Default")
      (node (ref "U16") (pin "16") (pinfunction "GP6_16") (pintype "bidirectional"))
    )
    (net (code "71") (name "unconnected-(U16-GP7-Pad17)") (class "Default")
      (node (ref "U16") (pin "17") (pinfunction "GP7_17") (pintype "bidirectional"))
    )
    (net (code "72") (name "unconnected-(U17-INTA-Pad8)") (class "Default")
      (node (ref "U17") (pin "8") (pinfunction "INTA_8") (pintype "output"))
    )
  )
)
